# Variable_Voltage.net
KiCad netlist of a schematic drawn in EAGLE
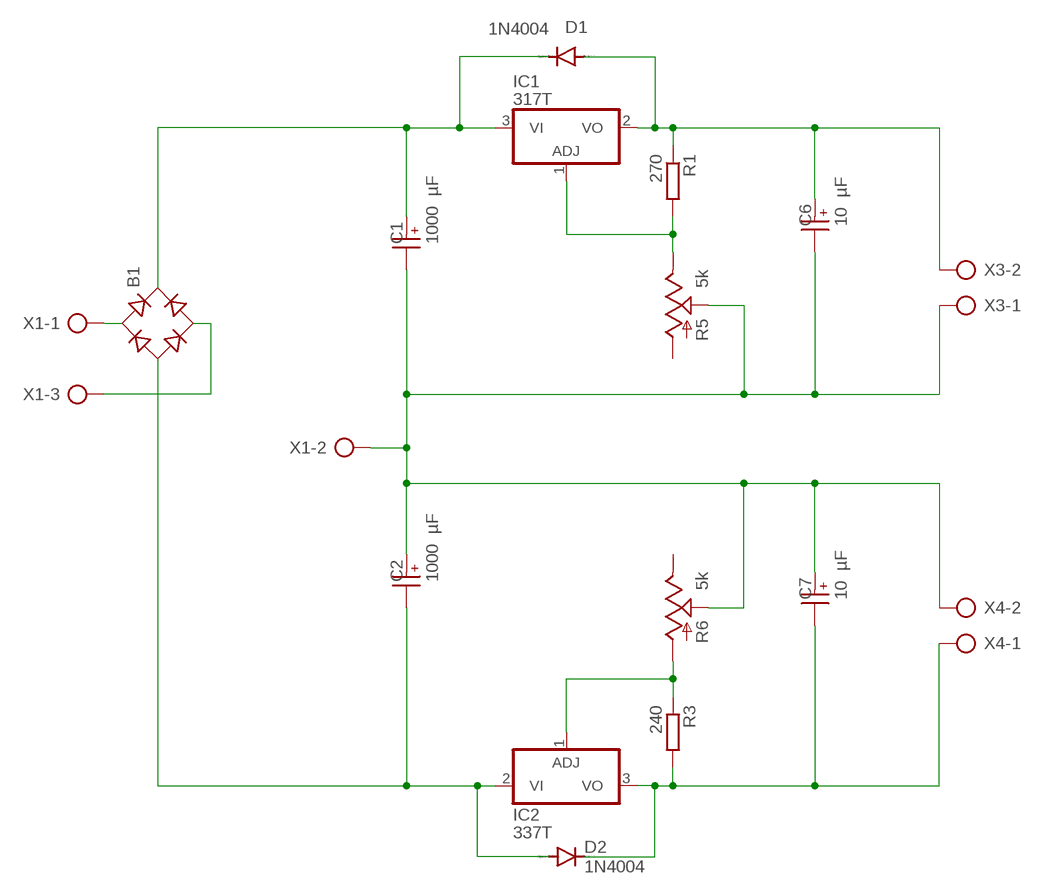
[diagram p0: schematic, sheet 1]

(export (version "E")
  (design (tool "Eeschema 10.0.6"))
  (components
    (comp (ref "B1")
      (value "RB1A")
      (footprint "eagle-import:RB1A")
      (libsource (lib "eagle-import") (part "RB1A"))
    )
    (comp (ref "C1")
      (value "1000 µF")
      (footprint "eagle-import:WCAP-ATG8_10X12.5(DXL)")
      (libsource (lib "eagle-import") (part "WCAP-ATG8_10X12.5_860010275016"))
    )
    (comp (ref "C2")
      (value "1000 µF")
      (footprint "eagle-import:WCAP-ATG8_10X12.5(DXL)")
      (libsource (lib "eagle-import") (part "WCAP-ATG8_10X12.5_860010275016"))
    )
    (comp (ref "C6")
      (value "10 µF")
      (footprint "eagle-import:WCAP-ATG8_5X11(DXL)")
      (libsource (lib "eagle-import") (part "WCAP-ATG8_5X11_860010772009"))
    )
    (comp (ref "C7")
      (value "10 µF")
      (footprint "eagle-import:WCAP-ATG8_5X11(DXL)")
      (libsource (lib "eagle-import") (part "WCAP-ATG8_5X11_860010772009"))
    )
    (comp (ref "D1")
      (value "1N4004")
      (footprint "eagle-import:DO41-10")
      (libsource (lib "eagle-import") (part "1N4004"))
    )
    (comp (ref "D2")
      (value "1N4004")
      (footprint "eagle-import:DO41-10")
      (libsource (lib "eagle-import") (part "1N4004"))
    )
    (comp (ref "IC1")
      (value "317T")
      (footprint "eagle-import:TO220H")
      (libsource (lib "eagle-import") (part "317T"))
    )
    (comp (ref "IC2")
      (value "337T")
      (footprint "eagle-import:TO220H")
      (libsource (lib "eagle-import") (part "337T"))
    )
    (comp (ref "R1")
      (value "270")
      (footprint "eagle-import:0204_7")
      (libsource (lib "eagle-import") (part "R-EU_0204/7"))
    )
    (comp (ref "R3")
      (value "240")
      (footprint "eagle-import:0204_7")
      (libsource (lib "eagle-import") (part "R-EU_0204/7"))
    )
    (comp (ref "R5")
      (value "5k")
      (footprint "eagle-import:CA9V")
      (libsource (lib "eagle-import") (part "TRIM_US-CA9V"))
    )
    (comp (ref "R6")
      (value "5k")
      (footprint "eagle-import:CA9V")
      (libsource (lib "eagle-import") (part "TRIM_US-CA9V"))
    )
    (comp (ref "X1")
      (value "AK300/3")
      (footprint "eagle-import:AK300_3")
      (libsource (lib "eagle-import") (part "AK300/3"))
    )
    (comp (ref "X3")
      (value "AK300/2")
      (footprint "eagle-import:AK300_2")
      (libsource (lib "eagle-import") (part "AK300/2"))
    )
    (comp (ref "X4")
      (value "AK300/2")
      (footprint "eagle-import:AK300_2")
      (libsource (lib "eagle-import") (part "AK300/2"))
    )
  )
  (nets
    (net (code "1") (name "Net-(C1-+)") (class "Default")
      (node (ref "B1") (pin "+") (pinfunction "+_+") (pintype "passive"))
      (node (ref "C1") (pin "1") (pinfunction "+_1") (pintype "passive"))
      (node (ref "D1") (pin "C") (pinfunction "C_C") (pintype "passive"))
      (node (ref "IC1") (pin "3") (pinfunction "VI_3") (pintype "input"))
    )
    (net (code "2") (name "Net-(C1--)") (class "Default")
      (node (ref "C1") (pin "2") (pinfunction "-_2") (pintype "passive"))
      (node (ref "C2") (pin "1") (pinfunction "+_1") (pintype "passive"))
      (node (ref "C6") (pin "2") (pinfunction "-_2") (pintype "passive"))
      (node (ref "C7") (pin "1") (pinfunction "+_1") (pintype "passive"))
      (node (ref "R5") (pin "S") (pinfunction "S_S") (pintype "passive"))
      (node (ref "R6") (pin "S") (pinfunction "S_S") (pintype "passive"))
      (node (ref "X1") (pin "2") (pinfunction "KL_2") (pintype "passive"))
      (node (ref "X3") (pin "1") (pinfunction "KL_1") (pintype "passive"))
      (node (ref "X4") (pin "2") (pinfunction "KL_2") (pintype "passive"))
    )
    (net (code "3") (name "Net-(C2--)") (class "Default")
      (node (ref "B1") (pin "-") (pinfunction "-_-") (pintype "passive"))
      (node (ref "C2") (pin "2") (pinfunction "-_2") (pintype "passive"))
      (node (ref "D2") (pin "A") (pinfunction "A_A") (pintype "passive"))
      (node (ref "IC2") (pin "2") (pinfunction "VI_2") (pintype "input"))
    )
    (net (code "4") (name "Net-(C6-+)") (class "Default")
      (node (ref "C6") (pin "1") (pinfunction "+_1") (pintype "passive"))
      (node (ref "D1") (pin "A") (pinfunction "A_A") (pintype "passive"))
      (node (ref "IC1") (pin "2") (pinfunction "VO_2") (pintype "passive"))
      (node (ref "R1") (pin "1") (pinfunction "1_1") (pintype "passive"))
      (node (ref "X3") (pin "2") (pinfunction "KL_2") (pintype "passive"))
    )
    (net (code "5") (name "Net-(C7--)") (class "Default")
      (node (ref "C7") (pin "2") (pinfunction "-_2") (pintype "passive"))
      (node (ref "D2") (pin "C") (pinfunction "C_C") (pintype "passive"))
      (node (ref "IC2") (pin "3") (pinfunction "VO_3") (pintype "passive"))
      (node (ref "R3") (pin "2") (pinfunction "2_2") (pintype "passive"))
      (node (ref "X4") (pin "1") (pinfunction "KL_1") (pintype "passive"))
    )
    (net (code "6") (name "Net-(IC1-ADJ)") (class "Default")
      (node (ref "IC1") (pin "1") (pinfunction "ADJ_1") (pintype "input"))
      (node (ref "R1") (pin "2") (pinfunction "2_2") (pintype "passive"))
      (node (ref "R5") (pin "E") (pinfunction "E_E") (pintype "passive"))
    )
    (net (code "7") (name "Net-(IC2-ADJ)") (class "Default")
      (node (ref "IC2") (pin "1") (pinfunction "ADJ_1") (pintype "input"))
      (node (ref "R3") (pin "1") (pinfunction "1_1") (pintype "passive"))
      (node (ref "R6") (pin "A") (pinfunction "A_A") (pintype "passive"))
    )
    (net (code "8") (name "Net-(X1A-KL)") (class "Default")
      (node (ref "B1") (pin "AC1") (pinfunction "AC1_AC1") (pintype "passive"))
      (node (ref "X1") (pin "1") (pinfunction "KL_1") (pintype "passive"))
    )
    (net (code "9") (name "Net-(X1C-KL)") (class "Default")
      (node (ref "B1") (pin "AC2") (pinfunction "AC2_AC2") (pintype "passive"))
      (node (ref "X1") (pin "3") (pinfunction "KL_3") (pintype "passive"))
    )
    (net (code "10") (name "unconnected-(R5-PadA)") (class "Default")
      (node (ref "R5") (pin "A") (pinfunction "A_A") (pintype "passive"))
    )
    (net (code "11") (name "unconnected-(R6-PadE)") (class "Default")
      (node (ref "R6") (pin "E") (pinfunction "E_E") (pintype "passive"))
    )
  )
)
